# Raspberry_Pi_IMU_shield_vFinal.net
KiCad netlist of a schematic drawn in EAGLE
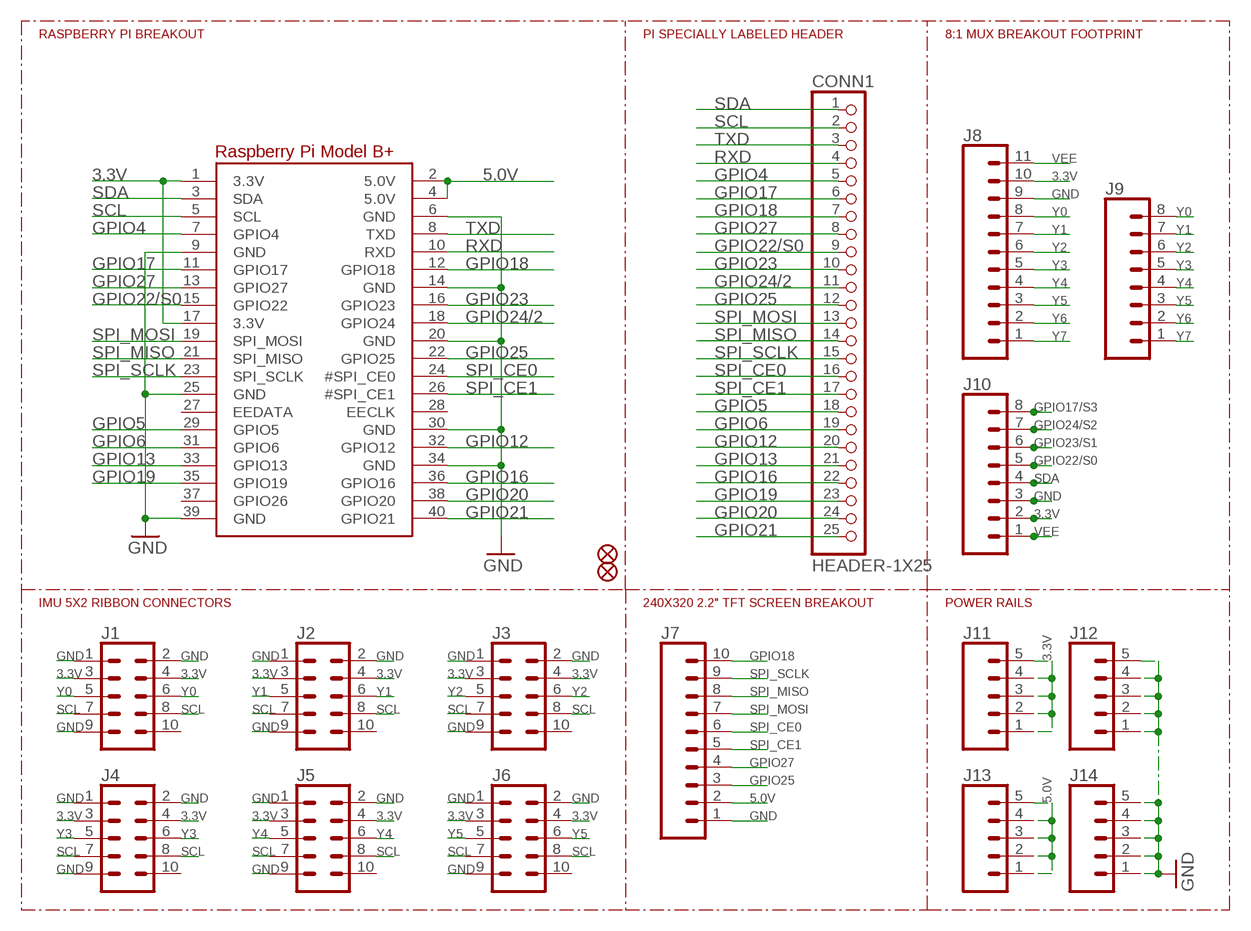
[diagram p0: schematic, sheet 1]

(export (version "E")
  (design (tool "Eeschema 10.0.6"))
  (components
    (comp (ref "CONN1")
      (value "HEADER-1X25")
      (footprint "eagle-import:1X25_ROUND_70MIL")
      (libsource (lib "eagle-import") (part "HEADER-1X25"))
    )
    (comp (ref "FID2")
      (value "FIDUCIAL\"\"")
      (footprint "eagle-import:FIDUCIAL_1MM")
      (libsource (lib "eagle-import") (part "FIDUCIAL{dblquote}{dblquote}"))
    )
    (comp (ref "FID3")
      (value "FIDUCIAL\"\"")
      (footprint "eagle-import:FIDUCIAL_1MM")
      (libsource (lib "eagle-import") (part "FIDUCIAL{dblquote}{dblquote}"))
    )
    (comp (ref "J1")
      (value "CONN_05X2SHD")
      (footprint "eagle-import:2X5-SHROUDED")
      (libsource (lib "eagle-import") (part "CONN_05X2SHD"))
    )
    (comp (ref "J2")
      (value "CONN_05X2SHD")
      (footprint "eagle-import:2X5-SHROUDED")
      (libsource (lib "eagle-import") (part "CONN_05X2SHD"))
    )
    (comp (ref "J3")
      (value "CONN_05X2SHD")
      (footprint "eagle-import:2X5-SHROUDED")
      (libsource (lib "eagle-import") (part "CONN_05X2SHD"))
    )
    (comp (ref "J4")
      (value "CONN_05X2SHD")
      (footprint "eagle-import:2X5-SHROUDED")
      (libsource (lib "eagle-import") (part "CONN_05X2SHD"))
    )
    (comp (ref "J5")
      (value "CONN_05X2SHD")
      (footprint "eagle-import:2X5-SHROUDED")
      (libsource (lib "eagle-import") (part "CONN_05X2SHD"))
    )
    (comp (ref "J6")
      (value "CONN_05X2SHD")
      (footprint "eagle-import:2X5-SHROUDED")
      (libsource (lib "eagle-import") (part "CONN_05X2SHD"))
    )
    (comp (ref "J7")
      (value "CONN_10LOCK")
      (footprint "eagle-import:1X10_LOCK")
      (libsource (lib "eagle-import") (part "CONN_10LOCK"))
    )
    (comp (ref "J8")
      (value "CONN_111X11_NO_SILK_KIT")
      (footprint "eagle-import:1X11_NO_SILK_KIT")
      (libsource (lib "eagle-import") (part "CONN_111X11_NO_SILK_KIT"))
    )
    (comp (ref "J9")
      (value "CONN_08NO_SILK_FEMALE_PTH")
      (footprint "eagle-import:1X08_NO_SILK")
      (libsource (lib "eagle-import") (part "CONN_08NO_SILK_FEMALE_PTH"))
    )
    (comp (ref "J10")
      (value "CONN_08NO_SILK_FEMALE_PTH")
      (footprint "eagle-import:1X08_NO_SILK")
      (libsource (lib "eagle-import") (part "CONN_08NO_SILK_FEMALE_PTH"))
    )
    (comp (ref "J11")
      (value "CONN_05")
      (footprint "eagle-import:1X05")
      (libsource (lib "eagle-import") (part "CONN_05"))
    )
    (comp (ref "J12")
      (value "CONN_05")
      (footprint "eagle-import:1X05")
      (libsource (lib "eagle-import") (part "CONN_05"))
    )
    (comp (ref "J13")
      (value "CONN_05")
      (footprint "eagle-import:1X05")
      (libsource (lib "eagle-import") (part "CONN_05"))
    )
    (comp (ref "J14")
      (value "CONN_05")
      (footprint "eagle-import:1X05")
      (libsource (lib "eagle-import") (part "CONN_05"))
    )
    (comp (ref "RPI1")
      (value "RASPBERRYPI_BPLUS_HATNOSLOTS")
      (footprint "eagle-import:PI_HAT_NOSLOTS")
      (libsource (lib "eagle-import") (part "RASPBERRYPI_BPLUS_HATNOSLOTS"))
    )
  )
  (nets
    (net (code "1") (name "/3.3V") (class "Default")
      (node (ref "J1") (pin "3") (pinfunction "3_3") (pintype "passive"))
      (node (ref "J1") (pin "4") (pinfunction "4_4") (pintype "passive"))
      (node (ref "J10") (pin "2") (pinfunction "2_2") (pintype "passive"))
      (node (ref "J11") (pin "1") (pinfunction "1_1") (pintype "passive"))
      (node (ref "J11") (pin "2") (pinfunction "2_2") (pintype "passive"))
      (node (ref "J11") (pin "3") (pinfunction "3_3") (pintype "passive"))
      (node (ref "J11") (pin "4") (pinfunction "4_4") (pintype "passive"))
      (node (ref "J11") (pin "5") (pinfunction "5_5") (pintype "passive"))
      (node (ref "J2") (pin "3") (pinfunction "3_3") (pintype "passive"))
      (node (ref "J2") (pin "4") (pinfunction "4_4") (pintype "passive"))
      (node (ref "J3") (pin "3") (pinfunction "3_3") (pintype "passive"))
      (node (ref "J3") (pin "4") (pinfunction "4_4") (pintype "passive"))
      (node (ref "J4") (pin "3") (pinfunction "3_3") (pintype "passive"))
      (node (ref "J4") (pin "4") (pinfunction "4_4") (pintype "passive"))
      (node (ref "J5") (pin "3") (pinfunction "3_3") (pintype "passive"))
      (node (ref "J5") (pin "4") (pinfunction "4_4") (pintype "passive"))
      (node (ref "J6") (pin "3") (pinfunction "3_3") (pintype "passive"))
      (node (ref "J6") (pin "4") (pinfunction "4_4") (pintype "passive"))
      (node (ref "J8") (pin "10") (pinfunction "10_10") (pintype "passive"))
      (node (ref "RPI1") (pin "1") (pinfunction "3.3V_1") (pintype "power_in"))
      (node (ref "RPI1") (pin "17") (pinfunction "3.3V_17") (pintype "power_in"))
    )
    (net (code "2") (name "/5.0V") (class "Default")
      (node (ref "J13") (pin "1") (pinfunction "1_1") (pintype "passive"))
      (node (ref "J13") (pin "2") (pinfunction "2_2") (pintype "passive"))
      (node (ref "J13") (pin "3") (pinfunction "3_3") (pintype "passive"))
      (node (ref "J13") (pin "4") (pinfunction "4_4") (pintype "passive"))
      (node (ref "J13") (pin "5") (pinfunction "5_5") (pintype "passive"))
      (node (ref "J7") (pin "2") (pinfunction "2_2") (pintype "passive"))
      (node (ref "RPI1") (pin "2") (pinfunction "5.0V_2") (pintype "power_in"))
      (node (ref "RPI1") (pin "4") (pinfunction "5.0V_4") (pintype "power_in"))
    )
    (net (code "3") (name "/EECLK") (class "Default")
      (node (ref "RPI1") (pin "28") (pinfunction "EECLK_28") (pintype "power_in"))
    )
    (net (code "4") (name "/GPIO4") (class "Default")
      (node (ref "CONN1") (pin "5") (pinfunction "5_5") (pintype "passive"))
      (node (ref "RPI1") (pin "7") (pinfunction "GPIO4_7") (pintype "bidirectional"))
    )
    (net (code "5") (name "/GPIO5") (class "Default")
      (node (ref "CONN1") (pin "18") (pinfunction "18_18") (pintype "passive"))
      (node (ref "RPI1") (pin "29") (pinfunction "GPIO5_29") (pintype "bidirectional"))
    )
    (net (code "6") (name "/GPIO6") (class "Default")
      (node (ref "CONN1") (pin "19") (pinfunction "19_19") (pintype "passive"))
      (node (ref "RPI1") (pin "31") (pinfunction "GPIO6_31") (pintype "power_in"))
    )
    (net (code "7") (name "/GPIO12") (class "Default")
      (node (ref "CONN1") (pin "20") (pinfunction "20_20") (pintype "passive"))
      (node (ref "RPI1") (pin "32") (pinfunction "GPIO12_32") (pintype "bidirectional"))
    )
    (net (code "8") (name "/GPIO13") (class "Default")
      (node (ref "CONN1") (pin "21") (pinfunction "21_21") (pintype "passive"))
      (node (ref "RPI1") (pin "33") (pinfunction "GPIO13_33") (pintype "bidirectional"))
    )
    (net (code "9") (name "/GPIO16") (class "Default")
      (node (ref "CONN1") (pin "22") (pinfunction "22_22") (pintype "passive"))
      (node (ref "RPI1") (pin "36") (pinfunction "GPIO16_36") (pintype "power_in"))
    )
    (net (code "10") (name "/GPIO17") (class "Default")
      (node (ref "CONN1") (pin "6") (pinfunction "6_6") (pintype "passive"))
      (node (ref "RPI1") (pin "11") (pinfunction "GPIO17_11") (pintype "bidirectional"))
    )
    (net (code "11") (name "/GPIO17{slash}S3") (class "Default")
      (node (ref "J10") (pin "8") (pinfunction "8_8") (pintype "passive"))
    )
    (net (code "12") (name "/GPIO18") (class "Default")
      (node (ref "CONN1") (pin "7") (pinfunction "7_7") (pintype "passive"))
      (node (ref "J7") (pin "10") (pinfunction "10_10") (pintype "passive"))
      (node (ref "RPI1") (pin "12") (pinfunction "GPIO18_12") (pintype "bidirectional"))
    )
    (net (code "13") (name "/GPIO19") (class "Default")
      (node (ref "CONN1") (pin "23") (pinfunction "23_23") (pintype "passive"))
      (node (ref "RPI1") (pin "35") (pinfunction "GPIO19_35") (pintype "bidirectional"))
    )
    (net (code "14") (name "/GPIO20") (class "Default")
      (node (ref "CONN1") (pin "24") (pinfunction "24_24") (pintype "passive"))
      (node (ref "RPI1") (pin "38") (pinfunction "GPIO20_38") (pintype "bidirectional"))
    )
    (net (code "15") (name "/GPIO21") (class "Default")
      (node (ref "CONN1") (pin "25") (pinfunction "25_25") (pintype "passive"))
      (node (ref "RPI1") (pin "40") (pinfunction "GPIO21_40") (pintype "bidirectional"))
    )
    (net (code "16") (name "/GPIO22{slash}S0") (class "Default")
      (node (ref "CONN1") (pin "9") (pinfunction "9_9") (pintype "passive"))
      (node (ref "J10") (pin "5") (pinfunction "5_5") (pintype "passive"))
      (node (ref "RPI1") (pin "15") (pinfunction "GPIO22_15") (pintype "bidirectional"))
    )
    (net (code "17") (name "/GPIO23") (class "Default")
      (node (ref "CONN1") (pin "10") (pinfunction "10_10") (pintype "passive"))
      (node (ref "RPI1") (pin "16") (pinfunction "GPIO23_16") (pintype "bidirectional"))
    )
    (net (code "18") (name "/GPIO23{slash}S1") (class "Default")
      (node (ref "J10") (pin "6") (pinfunction "6_6") (pintype "passive"))
    )
    (net (code "19") (name "/GPIO24{slash}2") (class "Default")
      (node (ref "CONN1") (pin "11") (pinfunction "11_11") (pintype "passive"))
      (node (ref "RPI1") (pin "18") (pinfunction "GPIO24_18") (pintype "bidirectional"))
    )
    (net (code "20") (name "/GPIO24{slash}S2") (class "Default")
      (node (ref "J10") (pin "7") (pinfunction "7_7") (pintype "passive"))
    )
    (net (code "21") (name "/GPIO25") (class "Default")
      (node (ref "CONN1") (pin "12") (pinfunction "12_12") (pintype "passive"))
      (node (ref "J7") (pin "3") (pinfunction "3_3") (pintype "passive"))
      (node (ref "RPI1") (pin "22") (pinfunction "GPIO25_22") (pintype "bidirectional"))
    )
    (net (code "22") (name "/GPIO27") (class "Default")
      (node (ref "CONN1") (pin "8") (pinfunction "8_8") (pintype "passive"))
      (node (ref "J7") (pin "4") (pinfunction "4_4") (pintype "passive"))
      (node (ref "RPI1") (pin "13") (pinfunction "GPIO27_13") (pintype "bidirectional"))
    )
    (net (code "23") (name "/RXD") (class "Default")
      (node (ref "CONN1") (pin "4") (pinfunction "4_4") (pintype "passive"))
      (node (ref "RPI1") (pin "10") (pinfunction "RXD_10") (pintype "bidirectional"))
    )
    (net (code "24") (name "/SCL") (class "Default")
      (node (ref "CONN1") (pin "2") (pinfunction "2_2") (pintype "passive"))
      (node (ref "J1") (pin "7") (pinfunction "7_7") (pintype "passive"))
      (node (ref "J1") (pin "8") (pinfunction "8_8") (pintype "passive"))
      (node (ref "J2") (pin "7") (pinfunction "7_7") (pintype "passive"))
      (node (ref "J2") (pin "8") (pinfunction "8_8") (pintype "passive"))
      (node (ref "J3") (pin "7") (pinfunction "7_7") (pintype "passive"))
      (node (ref "J3") (pin "8") (pinfunction "8_8") (pintype "passive"))
      (node (ref "J4") (pin "7") (pinfunction "7_7") (pintype "passive"))
      (node (ref "J4") (pin "8") (pinfunction "8_8") (pintype "passive"))
      (node (ref "J5") (pin "7") (pinfunction "7_7") (pintype "passive"))
      (node (ref "J5") (pin "8") (pinfunction "8_8") (pintype "passive"))
      (node (ref "J6") (pin "7") (pinfunction "7_7") (pintype "passive"))
      (node (ref "J6") (pin "8") (pinfunction "8_8") (pintype "passive"))
      (node (ref "RPI1") (pin "5") (pinfunction "SCL_5") (pintype "bidirectional"))
    )
    (net (code "25") (name "/SDA") (class "Default")
      (node (ref "CONN1") (pin "1") (pinfunction "1_1") (pintype "passive"))
      (node (ref "J10") (pin "4") (pinfunction "4_4") (pintype "passive"))
      (node (ref "RPI1") (pin "3") (pinfunction "SDA_3") (pintype "bidirectional"))
    )
    (net (code "26") (name "/SPI_CE0") (class "Default")
      (node (ref "CONN1") (pin "16") (pinfunction "16_16") (pintype "passive"))
      (node (ref "J7") (pin "6") (pinfunction "6_6") (pintype "passive"))
      (node (ref "RPI1") (pin "24") (pinfunction "#SPI_CE0_24") (pintype "bidirectional"))
    )
    (net (code "27") (name "/SPI_CE1") (class "Default")
      (node (ref "CONN1") (pin "17") (pinfunction "17_17") (pintype "passive"))
      (node (ref "J7") (pin "5") (pinfunction "5_5") (pintype "passive"))
      (node (ref "RPI1") (pin "26") (pinfunction "#SPI_CE1_26") (pintype "bidirectional"))
    )
    (net (code "28") (name "/SPI_MISO") (class "Default")
      (node (ref "CONN1") (pin "14") (pinfunction "14_14") (pintype "passive"))
      (node (ref "J7") (pin "8") (pinfunction "8_8") (pintype "passive"))
      (node (ref "RPI1") (pin "21") (pinfunction "SPI_MISO_21") (pintype "bidirectional"))
    )
    (net (code "29") (name "/SPI_MOSI") (class "Default")
      (node (ref "CONN1") (pin "13") (pinfunction "13_13") (pintype "passive"))
      (node (ref "J7") (pin "7") (pinfunction "7_7") (pintype "passive"))
      (node (ref "RPI1") (pin "19") (pinfunction "SPI_MOSI_19") (pintype "bidirectional"))
    )
    (net (code "30") (name "/SPI_SCLK") (class "Default")
      (node (ref "CONN1") (pin "15") (pinfunction "15_15") (pintype "passive"))
      (node (ref "J7") (pin "9") (pinfunction "9_9") (pintype "passive"))
      (node (ref "RPI1") (pin "23") (pinfunction "SPI_SCLK_23") (pintype "bidirectional"))
    )
    (net (code "31") (name "/TXD") (class "Default")
      (node (ref "CONN1") (pin "3") (pinfunction "3_3") (pintype "passive"))
      (node (ref "RPI1") (pin "8") (pinfunction "TXD_8") (pintype "output"))
    )
    (net (code "32") (name "/VEE") (class "Default")
      (node (ref "J10") (pin "1") (pinfunction "1_1") (pintype "passive"))
      (node (ref "J8") (pin "11") (pinfunction "11_11") (pintype "passive"))
    )
    (net (code "33") (name "/Y0") (class "Default")
      (node (ref "J1") (pin "5") (pinfunction "5_5") (pintype "passive"))
      (node (ref "J1") (pin "6") (pinfunction "6_6") (pintype "passive"))
      (node (ref "J8") (pin "8") (pinfunction "8_8") (pintype "passive"))
      (node (ref "J9") (pin "8") (pinfunction "8_8") (pintype "passive"))
    )
    (net (code "34") (name "/Y1") (class "Default")
      (node (ref "J2") (pin "5") (pinfunction "5_5") (pintype "passive"))
      (node (ref "J2") (pin "6") (pinfunction "6_6") (pintype "passive"))
      (node (ref "J8") (pin "7") (pinfunction "7_7") (pintype "passive"))
      (node (ref "J9") (pin "7") (pinfunction "7_7") (pintype "passive"))
    )
    (net (code "35") (name "/Y2") (class "Default")
      (node (ref "J3") (pin "5") (pinfunction "5_5") (pintype "passive"))
      (node (ref "J3") (pin "6") (pinfunction "6_6") (pintype "passive"))
      (node (ref "J8") (pin "6") (pinfunction "6_6") (pintype "passive"))
      (node (ref "J9") (pin "6") (pinfunction "6_6") (pintype "passive"))
    )
    (net (code "36") (name "/Y3") (class "Default")
      (node (ref "J4") (pin "5") (pinfunction "5_5") (pintype "passive"))
      (node (ref "J4") (pin "6") (pinfunction "6_6") (pintype "passive"))
      (node (ref "J8") (pin "5") (pinfunction "5_5") (pintype "passive"))
      (node (ref "J9") (pin "5") (pinfunction "5_5") (pintype "passive"))
    )
    (net (code "37") (name "/Y4") (class "Default")
      (node (ref "J5") (pin "5") (pinfunction "5_5") (pintype "passive"))
      (node (ref "J5") (pin "6") (pinfunction "6_6") (pintype "passive"))
      (node (ref "J8") (pin "4") (pinfunction "4_4") (pintype "passive"))
      (node (ref "J9") (pin "4") (pinfunction "4_4") (pintype "passive"))
    )
    (net (code "38") (name "/Y5") (class "Default")
      (node (ref "J6") (pin "5") (pinfunction "5_5") (pintype "passive"))
      (node (ref "J6") (pin "6") (pinfunction "6_6") (pintype "passive"))
      (node (ref "J8") (pin "3") (pinfunction "3_3") (pintype "passive"))
      (node (ref "J9") (pin "3") (pinfunction "3_3") (pintype "passive"))
    )
    (net (code "39") (name "/Y6") (class "Default")
      (node (ref "J8") (pin "2") (pinfunction "2_2") (pintype "passive"))
      (node (ref "J9") (pin "2") (pinfunction "2_2") (pintype "passive"))
    )
    (net (code "40") (name "/Y7") (class "Default")
      (node (ref "J8") (pin "1") (pinfunction "1_1") (pintype "passive"))
      (node (ref "J9") (pin "1") (pinfunction "1_1") (pintype "passive"))
    )
    (net (code "41") (name "GND") (class "Default")
      (node (ref "J1") (pin "1") (pinfunction "1_1") (pintype "passive"))
      (node (ref "J1") (pin "2") (pinfunction "2_2") (pintype "passive"))
      (node (ref "J1") (pin "9") (pinfunction "9_9") (pintype "passive"))
      (node (ref "J10") (pin "3") (pinfunction "3_3") (pintype "passive"))
      (node (ref "J12") (pin "1") (pinfunction "1_1") (pintype "passive"))
      (node (ref "J12") (pin "2") (pinfunction "2_2") (pintype "passive"))
      (node (ref "J12") (pin "3") (pinfunction "3_3") (pintype "passive"))
      (node (ref "J12") (pin "4") (pinfunction "4_4") (pintype "passive"))
      (node (ref "J12") (pin "5") (pinfunction "5_5") (pintype "passive"))
      (node (ref "J14") (pin "1") (pinfunction "1_1") (pintype "passive"))
      (node (ref "J14") (pin "2") (pinfunction "2_2") (pintype "passive"))
      (node (ref "J14") (pin "3") (pinfunction "3_3") (pintype "passive"))
      (node (ref "J14") (pin "4") (pinfunction "4_4") (pintype "passive"))
      (node (ref "J14") (pin "5") (pinfunction "5_5") (pintype "passive"))
      (node (ref "J2") (pin "1") (pinfunction "1_1") (pintype "passive"))
      (node (ref "J2") (pin "2") (pinfunction "2_2") (pintype "passive"))
      (node (ref "J2") (pin "9") (pinfunction "9_9") (pintype "passive"))
      (node (ref "J3") (pin "1") (pinfunction "1_1") (pintype "passive"))
      (node (ref "J3") (pin "2") (pinfunction "2_2") (pintype "passive"))
      (node (ref "J3") (pin "9") (pinfunction "9_9") (pintype "passive"))
      (node (ref "J4") (pin "1") (pinfunction "1_1") (pintype "passive"))
      (node (ref "J4") (pin "2") (pinfunction "2_2") (pintype "passive"))
      (node (ref "J4") (pin "9") (pinfunction "9_9") (pintype "passive"))
      (node (ref "J5") (pin "1") (pinfunction "1_1") (pintype "passive"))
      (node (ref "J5") (pin "2") (pinfunction "2_2") (pintype "passive"))
      (node (ref "J5") (pin "9") (pinfunction "9_9") (pintype "passive"))
      (node (ref "J6") (pin "1") (pinfunction "1_1") (pintype "passive"))
      (node (ref "J6") (pin "2") (pinfunction "2_2") (pintype "passive"))
      (node (ref "J6") (pin "9") (pinfunction "9_9") (pintype "passive"))
      (node (ref "J7") (pin "1") (pinfunction "1_1") (pintype "passive"))
      (node (ref "J8") (pin "9") (pinfunction "9_9") (pintype "passive"))
      (node (ref "RPI1") (pin "14") (pinfunction "GND_14") (pintype "power_in"))
      (node (ref "RPI1") (pin "20") (pinfunction "GND_20") (pintype "power_in"))
      (node (ref "RPI1") (pin "25") (pinfunction "GND_25") (pintype "power_in"))
      (node (ref "RPI1") (pin "30") (pinfunction "GND_30") (pintype "bidirectional"))
      (node (ref "RPI1") (pin "34") (pinfunction "GND_34") (pintype "bidirectional"))
      (node (ref "RPI1") (pin "39") (pinfunction "GND_39") (pintype "power_in"))
      (node (ref "RPI1") (pin "6") (pinfunction "GND_6") (pintype "power_in"))
      (node (ref "RPI1") (pin "9") (pinfunction "GND_9") (pintype "power_in"))
    )
    (net (code "42") (name "unconnected-(J1-Pad10)") (class "Default")
      (node (ref "J1") (pin "10") (pinfunction "10_10") (pintype "passive"))
    )
    (net (code "43") (name "unconnected-(J2-Pad10)") (class "Default")
      (node (ref "J2") (pin "10") (pinfunction "10_10") (pintype "passive"))
    )
    (net (code "44") (name "unconnected-(J3-Pad10)") (class "Default")
      (node (ref "J3") (pin "10") (pinfunction "10_10") (pintype "passive"))
    )
    (net (code "45") (name "unconnected-(J4-Pad10)") (class "Default")
      (node (ref "J4") (pin "10") (pinfunction "10_10") (pintype "passive"))
    )
    (net (code "46") (name "unconnected-(J5-Pad10)") (class "Default")
      (node (ref "J5") (pin "10") (pinfunction "10_10") (pintype "passive"))
    )
    (net (code "47") (name "unconnected-(J6-Pad10)") (class "Default")
      (node (ref "J6") (pin "10") (pinfunction "10_10") (pintype "passive"))
    )
    (net (code "48") (name "unconnected-(RPI1-EEDATA-Pad27)") (class "Default")
      (node (ref "RPI1") (pin "27") (pinfunction "EEDATA_27") (pintype "bidirectional"))
    )
    (net (code "49") (name "unconnected-(RPI1-GPIO26-Pad37)") (class "Default")
      (node (ref "RPI1") (pin "37") (pinfunction "GPIO26_37") (pintype "bidirectional"))
    )
  )
)
